# Power_Switching_Circuit_rev1.net
KiCad netlist of a schematic drawn in EAGLE
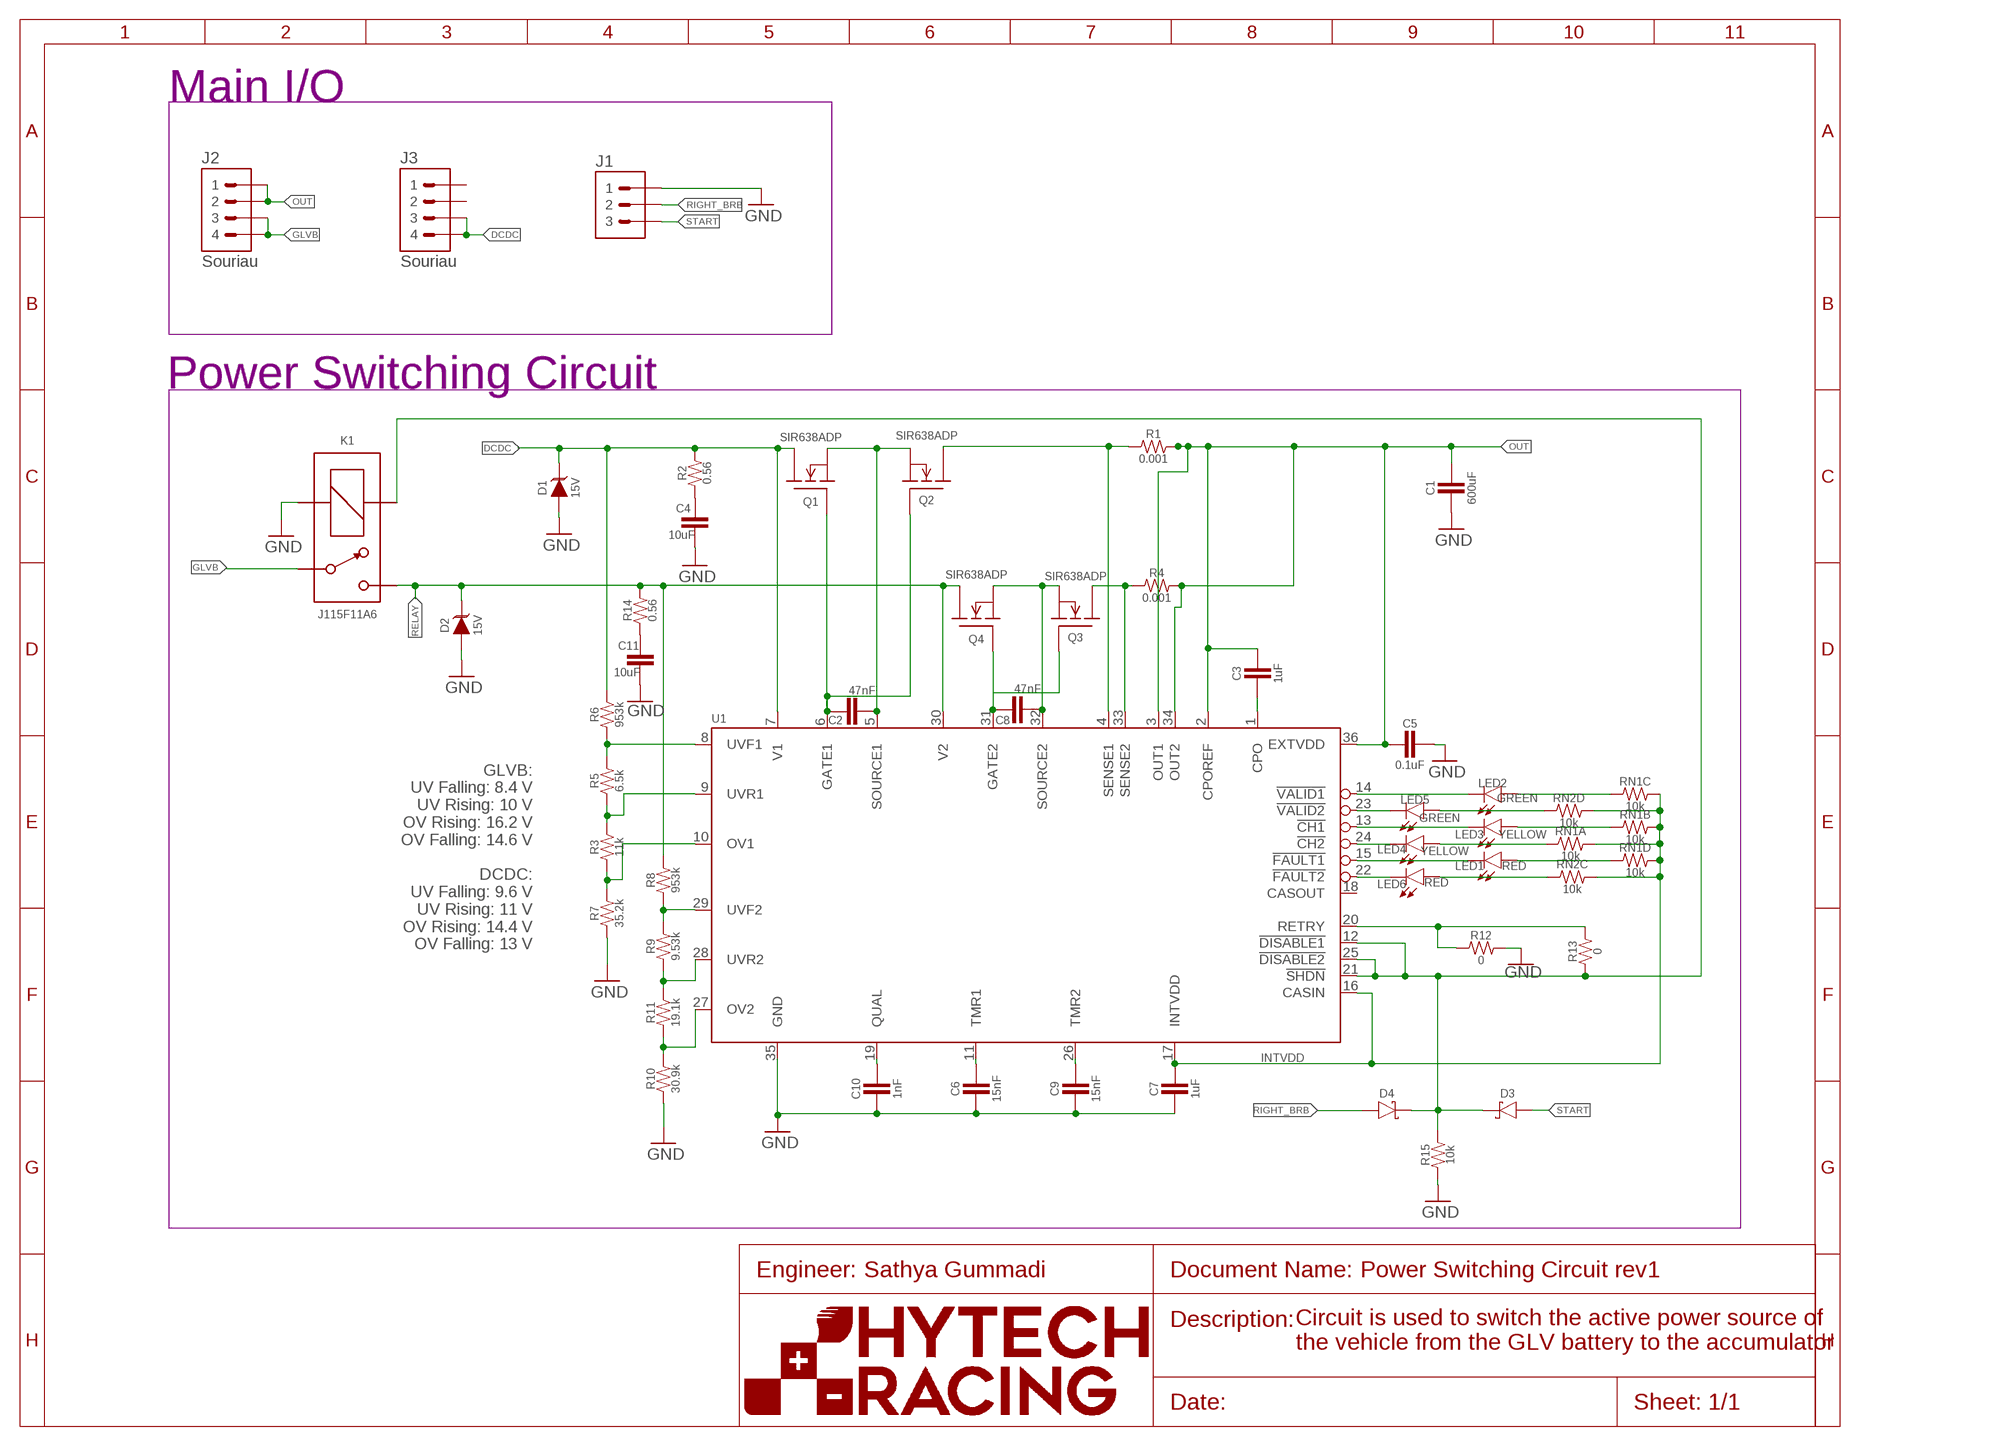
[diagram p0: schematic, sheet 1]

(export (version "E")
  (design (tool "Eeschema 10.0.6"))
  (components
    (comp (ref "C1")
      (value "600uF")
      (footprint "eagle-import:0603-CAP")
      (libsource (lib "eagle-import") (part "CAP0603-CAP"))
    )
    (comp (ref "C2")
      (value "47nF")
      (footprint "eagle-import:0603-CAP")
      (libsource (lib "eagle-import") (part "CAP0603-CAP"))
    )
    (comp (ref "C3")
      (value "1uF")
      (footprint "eagle-import:0603-CAP")
      (libsource (lib "eagle-import") (part "CAP0603-CAP"))
    )
    (comp (ref "C4")
      (value "10uF")
      (footprint "eagle-import:0603-CAP")
      (libsource (lib "eagle-import") (part "CAP0603-CAP"))
    )
    (comp (ref "C5")
      (value "0.1uF")
      (footprint "eagle-import:0603-CAP")
      (libsource (lib "eagle-import") (part "CAP0603-CAP"))
    )
    (comp (ref "C6")
      (value "15nF")
      (footprint "eagle-import:0603-CAP")
      (libsource (lib "eagle-import") (part "CAP0603-CAP"))
    )
    (comp (ref "C7")
      (value "1uF")
      (footprint "eagle-import:0603-CAP")
      (libsource (lib "eagle-import") (part "CAP0603-CAP"))
    )
    (comp (ref "C8")
      (value "47nF")
      (footprint "eagle-import:0603-CAP")
      (libsource (lib "eagle-import") (part "CAP0603-CAP"))
    )
    (comp (ref "C9")
      (value "15nF")
      (footprint "eagle-import:0603-CAP")
      (libsource (lib "eagle-import") (part "CAP0603-CAP"))
    )
    (comp (ref "C10")
      (value "1nF")
      (footprint "eagle-import:0603-CAP")
      (libsource (lib "eagle-import") (part "CAP0603-CAP"))
    )
    (comp (ref "C11")
      (value "10uF")
      (footprint "eagle-import:0603-CAP")
      (libsource (lib "eagle-import") (part "CAP0603-CAP"))
    )
    (comp (ref "D1")
      (value "TVS_15V")
      (footprint "eagle-import:SOT-23")
      (fields
        (field (name "MANUFACTURER") "Vishay General Semiconductor - Diodes Division")
        (field (name "MPN") "GSOT15-E3-08")
        (field (name "VOLTAGE") "15V")
      )
      (libsource (lib "eagle-import") (part "TVS_15V"))
    )
    (comp (ref "D2")
      (value "TVS_15V")
      (footprint "eagle-import:SOT-23")
      (fields
        (field (name "MANUFACTURER") "Vishay General Semiconductor - Diodes Division")
        (field (name "MPN") "GSOT15-E3-08")
        (field (name "VOLTAGE") "15V")
      )
      (libsource (lib "eagle-import") (part "TVS_15V"))
    )
    (comp (ref "D3")
      (value "SCHOTTKY")
      (footprint "eagle-import:CLP1608-2L")
      (fields
        (field (name "MANUFACTURER") "Vishay General Semiconductor - Diodes Division")
        (field (name "MPN") "VSKY20401608-G4-08")
      )
      (libsource (lib "eagle-import") (part "SCHOTTKY"))
    )
    (comp (ref "D4")
      (value "SCHOTTKY")
      (footprint "eagle-import:CLP1608-2L")
      (fields
        (field (name "MANUFACTURER") "Vishay General Semiconductor - Diodes Division")
        (field (name "MPN") "VSKY20401608-G4-08")
      )
      (libsource (lib "eagle-import") (part "SCHOTTKY"))
    )
    (comp (ref "J1")
      (value "CONNECTOR-3_")
      (footprint "eagle-import:SOURIAU_04-35")
      (libsource (lib "eagle-import") (part "CONNECTOR-3_?"))
    )
    (comp (ref "J2")
      (value "CONNECTOR-4_SOURIAU_")
      (footprint "eagle-import:SOURIAU_12-04")
      (fields
        (field (name "MODEL") "Souriau")
        (field (name "MANUFACTURER") "Souriau")
        (field (name "MPN") "8STA21204PN ")
      )
      (libsource (lib "eagle-import") (part "CONNECTOR-4_?_SOURIAU"))
    )
    (comp (ref "J3")
      (value "CONNECTOR-4_SOURIAU_")
      (footprint "eagle-import:SOURIAU_12-04")
      (fields
        (field (name "MODEL") "Souriau")
        (field (name "MANUFACTURER") "Souriau")
        (field (name "MPN") "8STA21204PN ")
      )
      (libsource (lib "eagle-import") (part "CONNECTOR-4_?_SOURIAU"))
    )
    (comp (ref "K1")
      (value "J115F11A6")
      (footprint "eagle-import:J115F11A_6_")
      (libsource (lib "eagle-import") (part "J115F11A6"))
    )
    (comp (ref "LED1")
      (value "RED")
      (footprint "eagle-import:LED-603")
      (libsource (lib "eagle-import") (part "LED-0603"))
    )
    (comp (ref "LED2")
      (value "GREEN")
      (footprint "eagle-import:LED-603")
      (libsource (lib "eagle-import") (part "LED-0603"))
    )
    (comp (ref "LED3")
      (value "YELLOW")
      (footprint "eagle-import:LED-603")
      (libsource (lib "eagle-import") (part "LED-0603"))
    )
    (comp (ref "LED4")
      (value "YELLOW")
      (footprint "eagle-import:LED-603")
      (libsource (lib "eagle-import") (part "LED-0603"))
    )
    (comp (ref "LED5")
      (value "GREEN")
      (footprint "eagle-import:LED-603")
      (libsource (lib "eagle-import") (part "LED-0603"))
    )
    (comp (ref "LED6")
      (value "RED")
      (footprint "eagle-import:LED-603")
      (libsource (lib "eagle-import") (part "LED-0603"))
    )
    (comp (ref "Q1")
      (value "SIR638ADP")
      (footprint "eagle-import:POWERPAK_SO-8")
      (libsource (lib "eagle-import") (part "SIR638ADP"))
    )
    (comp (ref "Q2")
      (value "SIR638ADP")
      (footprint "eagle-import:POWERPAK_SO-8")
      (libsource (lib "eagle-import") (part "SIR638ADP"))
    )
    (comp (ref "Q3")
      (value "SIR638ADP")
      (footprint "eagle-import:POWERPAK_SO-8")
      (libsource (lib "eagle-import") (part "SIR638ADP"))
    )
    (comp (ref "Q4")
      (value "SIR638ADP")
      (footprint "eagle-import:POWERPAK_SO-8")
      (libsource (lib "eagle-import") (part "SIR638ADP"))
    )
    (comp (ref "R1")
      (value "0.001")
      (footprint "eagle-import:5930-SENSE_RES")
      (libsource (lib "eagle-import") (part "RESISTOR5930-SENSE_RES"))
    )
    (comp (ref "R2")
      (value "0.56")
      (footprint "eagle-import:0805")
      (libsource (lib "eagle-import") (part "RESISTOR0805"))
    )
    (comp (ref "R3")
      (value "11k")
      (footprint "eagle-import:0603-RES")
      (libsource (lib "eagle-import") (part "RESISTOR0603"))
    )
    (comp (ref "R4")
      (value "0.001")
      (footprint "eagle-import:5930-SENSE_RES")
      (libsource (lib "eagle-import") (part "RESISTOR5930-SENSE_RES"))
    )
    (comp (ref "R5")
      (value "6.5k")
      (footprint "eagle-import:0603-RES")
      (libsource (lib "eagle-import") (part "RESISTOR0603"))
    )
    (comp (ref "R6")
      (value "953k")
      (footprint "eagle-import:0603-RES")
      (libsource (lib "eagle-import") (part "RESISTOR0603"))
    )
    (comp (ref "R7")
      (value "35.2k")
      (footprint "eagle-import:0603-RES")
      (libsource (lib "eagle-import") (part "RESISTOR0603"))
    )
    (comp (ref "R8")
      (value "953k")
      (footprint "eagle-import:0603-RES")
      (libsource (lib "eagle-import") (part "RESISTOR0603"))
    )
    (comp (ref "R9")
      (value "9.53k")
      (footprint "eagle-import:0603-RES")
      (libsource (lib "eagle-import") (part "RESISTOR0603"))
    )
    (comp (ref "R10")
      (value "30.9k")
      (footprint "eagle-import:0603-RES")
      (libsource (lib "eagle-import") (part "RESISTOR0603"))
    )
    (comp (ref "R11")
      (value "19.1k")
      (footprint "eagle-import:0603-RES")
      (libsource (lib "eagle-import") (part "RESISTOR0603"))
    )
    (comp (ref "R12")
      (value "0")
      (footprint "eagle-import:0603-RES")
      (libsource (lib "eagle-import") (part "RESISTOR0603"))
    )
    (comp (ref "R13")
      (value "0")
      (footprint "eagle-import:0603-RES")
      (libsource (lib "eagle-import") (part "RESISTOR0603"))
    )
    (comp (ref "R14")
      (value "0.56")
      (footprint "eagle-import:0805")
      (libsource (lib "eagle-import") (part "RESISTOR0805"))
    )
    (comp (ref "R15")
      (value "10k")
      (footprint "eagle-import:0603-RES")
      (libsource (lib "eagle-import") (part "RESISTOR0603"))
    )
    (comp (ref "RN1")
      (value "RESISTOR_NETWORK_4_10K")
      (footprint "eagle-import:YC_TC164")
      (fields (field (name "RESISTANCE") "10k"))
      (libsource (lib "eagle-import") (part "RESISTOR_NETWORK_4_10K"))
    )
    (comp (ref "RN2")
      (value "RESISTOR_NETWORK_4_10K")
      (footprint "eagle-import:YC_TC164")
      (fields (field (name "RESISTANCE") "10k"))
      (libsource (lib "eagle-import") (part "RESISTOR_NETWORK_4_10K"))
    )
    (comp (ref "U1")
      (value "LTC4421")
      (footprint "eagle-import:SSOP-36")
      (libsource (lib "eagle-import") (part "LTC4421"))
    )
  )
  (nets
    (net (code "1") (name "/INTVDD") (class "Default")
      (node (ref "C7") (pin "1") (pinfunction "1_1") (pintype "passive"))
      (node (ref "RN1") (pin "5") (pinfunction "2_5") (pintype "passive"))
      (node (ref "RN1") (pin "6") (pinfunction "2_6") (pintype "passive"))
      (node (ref "RN1") (pin "7") (pinfunction "2_7") (pintype "passive"))
      (node (ref "RN1") (pin "8") (pinfunction "2_8") (pintype "passive"))
      (node (ref "RN2") (pin "5") (pinfunction "2_5") (pintype "passive"))
      (node (ref "RN2") (pin "6") (pinfunction "2_6") (pintype "passive"))
      (node (ref "U1") (pin "16") (pinfunction "CASIN_16") (pintype "input"))
      (node (ref "U1") (pin "17") (pinfunction "INTVDD_17") (pintype "power_in"))
    )
    (net (code "2") (name "DCDC") (class "Default")
      (node (ref "D1") (pin "3") (pinfunction "C_3") (pintype "passive"))
      (node (ref "J3") (pin "3") (pinfunction "3_3") (pintype "passive"))
      (node (ref "J3") (pin "4") (pinfunction "4_4") (pintype "passive"))
      (node (ref "Q1") (pin "D@5") (pinfunction "D_D@5") (pintype "passive"))
      (node (ref "Q1") (pin "D@6") (pinfunction "D_D@6") (pintype "passive"))
      (node (ref "Q1") (pin "D@7") (pinfunction "D_D@7") (pintype "passive"))
      (node (ref "Q1") (pin "D@8") (pinfunction "D_D@8") (pintype "passive"))
      (node (ref "Q1") (pin "D@PAD") (pinfunction "D_D@PAD") (pintype "passive"))
      (node (ref "R2") (pin "2") (pinfunction "2_2") (pintype "passive"))
      (node (ref "R6") (pin "2") (pinfunction "2_2") (pintype "passive"))
      (node (ref "U1") (pin "7") (pinfunction "V1_7") (pintype "input"))
    )
    (net (code "3") (name "GLVB") (class "Default")
      (node (ref "J2") (pin "3") (pinfunction "3_3") (pintype "passive"))
      (node (ref "J2") (pin "4") (pinfunction "4_4") (pintype "passive"))
      (node (ref "K1") (pin "CONTACT1") (pinfunction "P_CONTACT1") (pintype "bidirectional"))
    )
    (net (code "4") (name "GND") (class "Default")
      (node (ref "C1") (pin "2") (pinfunction "2_2") (pintype "passive"))
      (node (ref "C10") (pin "2") (pinfunction "2_2") (pintype "passive"))
      (node (ref "C11") (pin "2") (pinfunction "2_2") (pintype "passive"))
      (node (ref "C4") (pin "2") (pinfunction "2_2") (pintype "passive"))
      (node (ref "C5") (pin "1") (pinfunction "1_1") (pintype "passive"))
      (node (ref "C6") (pin "2") (pinfunction "2_2") (pintype "passive"))
      (node (ref "C7") (pin "2") (pinfunction "2_2") (pintype "passive"))
      (node (ref "C9") (pin "2") (pinfunction "2_2") (pintype "passive"))
      (node (ref "D1") (pin "1") (pinfunction "A_1") (pintype "passive"))
      (node (ref "D2") (pin "1") (pinfunction "A_1") (pintype "passive"))
      (node (ref "J1") (pin "A") (pinfunction "1_A") (pintype "passive"))
      (node (ref "K1") (pin "COIL2") (pinfunction "COIL-_COIL2") (pintype "bidirectional"))
      (node (ref "R10") (pin "1") (pinfunction "1_1") (pintype "passive"))
      (node (ref "R12") (pin "2") (pinfunction "2_2") (pintype "passive"))
      (node (ref "R15") (pin "1") (pinfunction "1_1") (pintype "passive"))
      (node (ref "R7") (pin "1") (pinfunction "1_1") (pintype "passive"))
      (node (ref "U1") (pin "35") (pinfunction "GND_35") (pintype "power_in"))
    )
    (net (code "5") (name "Net-(C4-Pad1)") (class "Default")
      (node (ref "C4") (pin "1") (pinfunction "1_1") (pintype "passive"))
      (node (ref "R2") (pin "1") (pinfunction "1_1") (pintype "passive"))
    )
    (net (code "6") (name "Net-(C11-Pad1)") (class "Default")
      (node (ref "C11") (pin "1") (pinfunction "1_1") (pintype "passive"))
      (node (ref "R14") (pin "1") (pinfunction "1_1") (pintype "passive"))
    )
    (net (code "7") (name "Net-(D3-C)") (class "Default")
      (node (ref "D3") (pin "2") (pinfunction "C_2") (pintype "passive"))
      (node (ref "D4") (pin "2") (pinfunction "C_2") (pintype "passive"))
      (node (ref "K1") (pin "COIL1") (pinfunction "COIL+_COIL1") (pintype "bidirectional"))
      (node (ref "R13") (pin "1") (pinfunction "1_1") (pintype "passive"))
      (node (ref "R15") (pin "2") (pinfunction "2_2") (pintype "passive"))
      (node (ref "U1") (pin "12") (pinfunction "~{DISABLE1}_12") (pintype "input"))
      (node (ref "U1") (pin "21") (pinfunction "~{SHDN}_21") (pintype "input"))
      (node (ref "U1") (pin "25") (pinfunction "~{DISABLE2}_25") (pintype "input"))
    )
    (net (code "8") (name "Net-(LED4-PadA)") (class "Default")
      (node (ref "LED4") (pin "A") (pinfunction "A_A") (pintype "passive"))
      (node (ref "RN1") (pin "1") (pinfunction "1_1") (pintype "passive"))
    )
    (net (code "9") (name "Net-(Q1-G)") (class "Default")
      (node (ref "C2") (pin "2") (pinfunction "2_2") (pintype "passive"))
      (node (ref "Q1") (pin "4") (pinfunction "G_4") (pintype "passive"))
      (node (ref "Q2") (pin "4") (pinfunction "G_4") (pintype "passive"))
      (node (ref "U1") (pin "6") (pinfunction "GATE1_6") (pintype "input"))
    )
    (net (code "10") (name "Net-(Q3-G)") (class "Default")
      (node (ref "C8") (pin "2") (pinfunction "2_2") (pintype "passive"))
      (node (ref "Q3") (pin "4") (pinfunction "G_4") (pintype "passive"))
      (node (ref "Q4") (pin "4") (pinfunction "G_4") (pintype "passive"))
      (node (ref "U1") (pin "31") (pinfunction "GATE2_31") (pintype "input"))
    )
    (net (code "11") (name "Net-(RN1B-1)") (class "Default")
      (node (ref "LED3") (pin "A") (pinfunction "A_A") (pintype "passive"))
      (node (ref "RN1") (pin "2") (pinfunction "1_2") (pintype "passive"))
    )
    (net (code "12") (name "Net-(RN1C-1)") (class "Default")
      (node (ref "LED2") (pin "A") (pinfunction "A_A") (pintype "passive"))
      (node (ref "RN1") (pin "3") (pinfunction "1_3") (pintype "passive"))
    )
    (net (code "13") (name "Net-(RN1D-1)") (class "Default")
      (node (ref "LED1") (pin "A") (pinfunction "A_A") (pintype "passive"))
      (node (ref "RN1") (pin "4") (pinfunction "1_4") (pintype "passive"))
    )
    (net (code "14") (name "Net-(RN2C-1)") (class "Default")
      (node (ref "LED6") (pin "A") (pinfunction "A_A") (pintype "passive"))
      (node (ref "RN2") (pin "3") (pinfunction "1_3") (pintype "passive"))
    )
    (net (code "15") (name "Net-(RN2D-1)") (class "Default")
      (node (ref "LED5") (pin "A") (pinfunction "A_A") (pintype "passive"))
      (node (ref "RN2") (pin "4") (pinfunction "1_4") (pintype "passive"))
    )
    (net (code "16") (name "Net-(U1-CPO)") (class "Default")
      (node (ref "C3") (pin "2") (pinfunction "2_2") (pintype "passive"))
      (node (ref "U1") (pin "1") (pinfunction "CPO_1") (pintype "input"))
    )
    (net (code "17") (name "Net-(U1-OV1)") (class "Default")
      (node (ref "R3") (pin "1") (pinfunction "1_1") (pintype "passive"))
      (node (ref "R7") (pin "2") (pinfunction "2_2") (pintype "passive"))
      (node (ref "U1") (pin "10") (pinfunction "OV1_10") (pintype "input"))
    )
    (net (code "18") (name "Net-(U1-OV2)") (class "Default")
      (node (ref "R10") (pin "2") (pinfunction "2_2") (pintype "passive"))
      (node (ref "R11") (pin "1") (pinfunction "1_1") (pintype "passive"))
      (node (ref "U1") (pin "27") (pinfunction "OV2_27") (pintype "input"))
    )
    (net (code "19") (name "Net-(U1-QUAL)") (class "Default")
      (node (ref "C10") (pin "1") (pinfunction "1_1") (pintype "passive"))
      (node (ref "U1") (pin "19") (pinfunction "QUAL_19") (pintype "bidirectional"))
    )
    (net (code "20") (name "Net-(U1-RETRY)") (class "Default")
      (node (ref "R12") (pin "1") (pinfunction "1_1") (pintype "passive"))
      (node (ref "R13") (pin "2") (pinfunction "2_2") (pintype "passive"))
      (node (ref "U1") (pin "20") (pinfunction "RETRY_20") (pintype "input"))
    )
    (net (code "21") (name "Net-(U1-SENSE1)") (class "Default")
      (node (ref "Q2") (pin "D@5") (pinfunction "D_D@5") (pintype "passive"))
      (node (ref "Q2") (pin "D@6") (pinfunction "D_D@6") (pintype "passive"))
      (node (ref "Q2") (pin "D@7") (pinfunction "D_D@7") (pintype "passive"))
      (node (ref "Q2") (pin "D@8") (pinfunction "D_D@8") (pintype "passive"))
      (node (ref "Q2") (pin "D@PAD") (pinfunction "D_D@PAD") (pintype "passive"))
      (node (ref "R1") (pin "1") (pinfunction "1_1") (pintype "passive"))
      (node (ref "U1") (pin "4") (pinfunction "SENSE1_4") (pintype "input"))
    )
    (net (code "22") (name "Net-(U1-SENSE2)") (class "Default")
      (node (ref "Q3") (pin "D@5") (pinfunction "D_D@5") (pintype "passive"))
      (node (ref "Q3") (pin "D@6") (pinfunction "D_D@6") (pintype "passive"))
      (node (ref "Q3") (pin "D@7") (pinfunction "D_D@7") (pintype "passive"))
      (node (ref "Q3") (pin "D@8") (pinfunction "D_D@8") (pintype "passive"))
      (node (ref "Q3") (pin "D@PAD") (pinfunction "D_D@PAD") (pintype "passive"))
      (node (ref "R4") (pin "1") (pinfunction "1_1") (pintype "passive"))
      (node (ref "U1") (pin "33") (pinfunction "SENSE2_33") (pintype "input"))
    )
    (net (code "23") (name "Net-(U1-SOURCE1)") (class "Default")
      (node (ref "C2") (pin "1") (pinfunction "1_1") (pintype "passive"))
      (node (ref "Q1") (pin "1") (pinfunction "S_1") (pintype "passive"))
      (node (ref "Q1") (pin "2") (pinfunction "S_2") (pintype "passive"))
      (node (ref "Q1") (pin "3") (pinfunction "S_3") (pintype "passive"))
      (node (ref "Q2") (pin "1") (pinfunction "S_1") (pintype "passive"))
      (node (ref "Q2") (pin "2") (pinfunction "S_2") (pintype "passive"))
      (node (ref "Q2") (pin "3") (pinfunction "S_3") (pintype "passive"))
      (node (ref "U1") (pin "5") (pinfunction "SOURCE1_5") (pintype "input"))
    )
    (net (code "24") (name "Net-(U1-SOURCE2)") (class "Default")
      (node (ref "C8") (pin "1") (pinfunction "1_1") (pintype "passive"))
      (node (ref "Q3") (pin "1") (pinfunction "S_1") (pintype "passive"))
      (node (ref "Q3") (pin "2") (pinfunction "S_2") (pintype "passive"))
      (node (ref "Q3") (pin "3") (pinfunction "S_3") (pintype "passive"))
      (node (ref "Q4") (pin "1") (pinfunction "S_1") (pintype "passive"))
      (node (ref "Q4") (pin "2") (pinfunction "S_2") (pintype "passive"))
      (node (ref "Q4") (pin "3") (pinfunction "S_3") (pintype "passive"))
      (node (ref "U1") (pin "32") (pinfunction "SOURCE2_32") (pintype "input"))
    )
    (net (code "25") (name "Net-(U1-TMR1)") (class "Default")
      (node (ref "C6") (pin "1") (pinfunction "1_1") (pintype "passive"))
      (node (ref "U1") (pin "11") (pinfunction "TMR1_11") (pintype "bidirectional"))
    )
    (net (code "26") (name "Net-(U1-TMR2)") (class "Default")
      (node (ref "C9") (pin "1") (pinfunction "1_1") (pintype "passive"))
      (node (ref "U1") (pin "26") (pinfunction "TMR2_26") (pintype "bidirectional"))
    )
    (net (code "27") (name "Net-(U1-UVF1)") (class "Default")
      (node (ref "R5") (pin "2") (pinfunction "2_2") (pintype "passive"))
      (node (ref "R6") (pin "1") (pinfunction "1_1") (pintype "passive"))
      (node (ref "U1") (pin "8") (pinfunction "UVF1_8") (pintype "input"))
    )
    (net (code "28") (name "Net-(U1-UVF2)") (class "Default")
      (node (ref "R8") (pin "1") (pinfunction "1_1") (pintype "passive"))
      (node (ref "R9") (pin "2") (pinfunction "2_2") (pintype "passive"))
      (node (ref "U1") (pin "29") (pinfunction "UVF2_29") (pintype "input"))
    )
    (net (code "29") (name "Net-(U1-UVR1)") (class "Default")
      (node (ref "R3") (pin "2") (pinfunction "2_2") (pintype "passive"))
      (node (ref "R5") (pin "1") (pinfunction "1_1") (pintype "passive"))
      (node (ref "U1") (pin "9") (pinfunction "UVR1_9") (pintype "input"))
    )
    (net (code "30") (name "Net-(U1-UVR2)") (class "Default")
      (node (ref "R11") (pin "2") (pinfunction "2_2") (pintype "passive"))
      (node (ref "R9") (pin "1") (pinfunction "1_1") (pintype "passive"))
      (node (ref "U1") (pin "28") (pinfunction "UVR2_28") (pintype "input"))
    )
    (net (code "31") (name "Net-(U1-~{CH1})") (class "Default")
      (node (ref "LED3") (pin "C") (pinfunction "C_C") (pintype "passive"))
      (node (ref "U1") (pin "13") (pinfunction "~{CH1}_13") (pintype "open_collector"))
    )
    (net (code "32") (name "Net-(U1-~{CH2})") (class "Default")
      (node (ref "LED4") (pin "C") (pinfunction "C_C") (pintype "passive"))
      (node (ref "U1") (pin "24") (pinfunction "~{CH2}_24") (pintype "open_collector"))
    )
    (net (code "33") (name "Net-(U1-~{FAULT1})") (class "Default")
      (node (ref "LED1") (pin "C") (pinfunction "C_C") (pintype "passive"))
      (node (ref "U1") (pin "15") (pinfunction "~{FAULT1}_15") (pintype "open_collector"))
    )
    (net (code "34") (name "Net-(U1-~{FAULT2})") (class "Default")
      (node (ref "LED6") (pin "C") (pinfunction "C_C") (pintype "passive"))
      (node (ref "U1") (pin "22") (pinfunction "~{FAULT2}_22") (pintype "open_collector"))
    )
    (net (code "35") (name "Net-(U1-~{VALID1})") (class "Default")
      (node (ref "LED2") (pin "C") (pinfunction "C_C") (pintype "passive"))
      (node (ref "U1") (pin "14") (pinfunction "~{VALID1}_14") (pintype "open_collector"))
    )
    (net (code "36") (name "Net-(U1-~{VALID2})") (class "Default")
      (node (ref "LED5") (pin "C") (pinfunction "C_C") (pintype "passive"))
      (node (ref "U1") (pin "23") (pinfunction "~{VALID2}_23") (pintype "open_collector"))
    )
    (net (code "37") (name "OUT") (class "Default")
      (node (ref "C1") (pin "1") (pinfunction "1_1") (pintype "passive"))
      (node (ref "C3") (pin "1") (pinfunction "1_1") (pintype "passive"))
      (node (ref "C5") (pin "2") (pinfunction "2_2") (pintype "passive"))
      (node (ref "J2") (pin "1") (pinfunction "1_1") (pintype "passive"))
      (node (ref "J2") (pin "2") (pinfunction "2_2") (pintype "passive"))
      (node (ref "R1") (pin "2") (pinfunction "2_2") (pintype "passive"))
      (node (ref "R4") (pin "2") (pinfunction "2_2") (pintype "passive"))
      (node (ref "U1") (pin "2") (pinfunction "CPOREF_2") (pintype "input"))
      (node (ref "U1") (pin "3") (pinfunction "OUT1_3") (pintype "input"))
      (node (ref "U1") (pin "34") (pinfunction "OUT2_34") (pintype "input"))
      (node (ref "U1") (pin "36") (pinfunction "EXTVDD_36") (pintype "power_in"))
    )
    (net (code "38") (name "RELAY") (class "Default")
      (node (ref "D2") (pin "3") (pinfunction "C_3") (pintype "passive"))
      (node (ref "K1") (pin "CONTACT2") (pinfunction "S_CONTACT2") (pintype "bidirectional"))
      (node (ref "Q4") (pin "D@5") (pinfunction "D_D@5") (pintype "passive"))
      (node (ref "Q4") (pin "D@6") (pinfunction "D_D@6") (pintype "passive"))
      (node (ref "Q4") (pin "D@7") (pinfunction "D_D@7") (pintype "passive"))
      (node (ref "Q4") (pin "D@8") (pinfunction "D_D@8") (pintype "passive"))
      (node (ref "Q4") (pin "D@PAD") (pinfunction "D_D@PAD") (pintype "passive"))
      (node (ref "R14") (pin "2") (pinfunction "2_2") (pintype "passive"))
      (node (ref "R8") (pin "2") (pinfunction "2_2") (pintype "passive"))
      (node (ref "U1") (pin "30") (pinfunction "V2_30") (pintype "input"))
    )
    (net (code "39") (name "RIGHT_BRB") (class "Default")
      (node (ref "D4") (pin "1") (pinfunction "A_1") (pintype "passive"))
      (node (ref "J1") (pin "B") (pinfunction "2_B") (pintype "passive"))
    )
    (net (code "40") (name "START") (class "Default")
      (node (ref "D3") (pin "1") (pinfunction "A_1") (pintype "passive"))
      (node (ref "J1") (pin "C") (pinfunction "3_C") (pintype "passive"))
    )
    (net (code "41") (name "unconnected-(J3-Pad1)") (class "Default")
      (node (ref "J3") (pin "1") (pinfunction "1_1") (pintype "passive"))
    )
    (net (code "42") (name "unconnected-(J3-Pad2)") (class "Default")
      (node (ref "J3") (pin "2") (pinfunction "2_2") (pintype "passive"))
    )
    (net (code "43") (name "unconnected-(U1-CASOUT-Pad18)") (class "Default")
      (node (ref "U1") (pin "18") (pinfunction "CASOUT_18") (pintype "output"))
    )
  )
)
